# Schematics.net
KiCad netlist of a schematic drawn in EAGLE
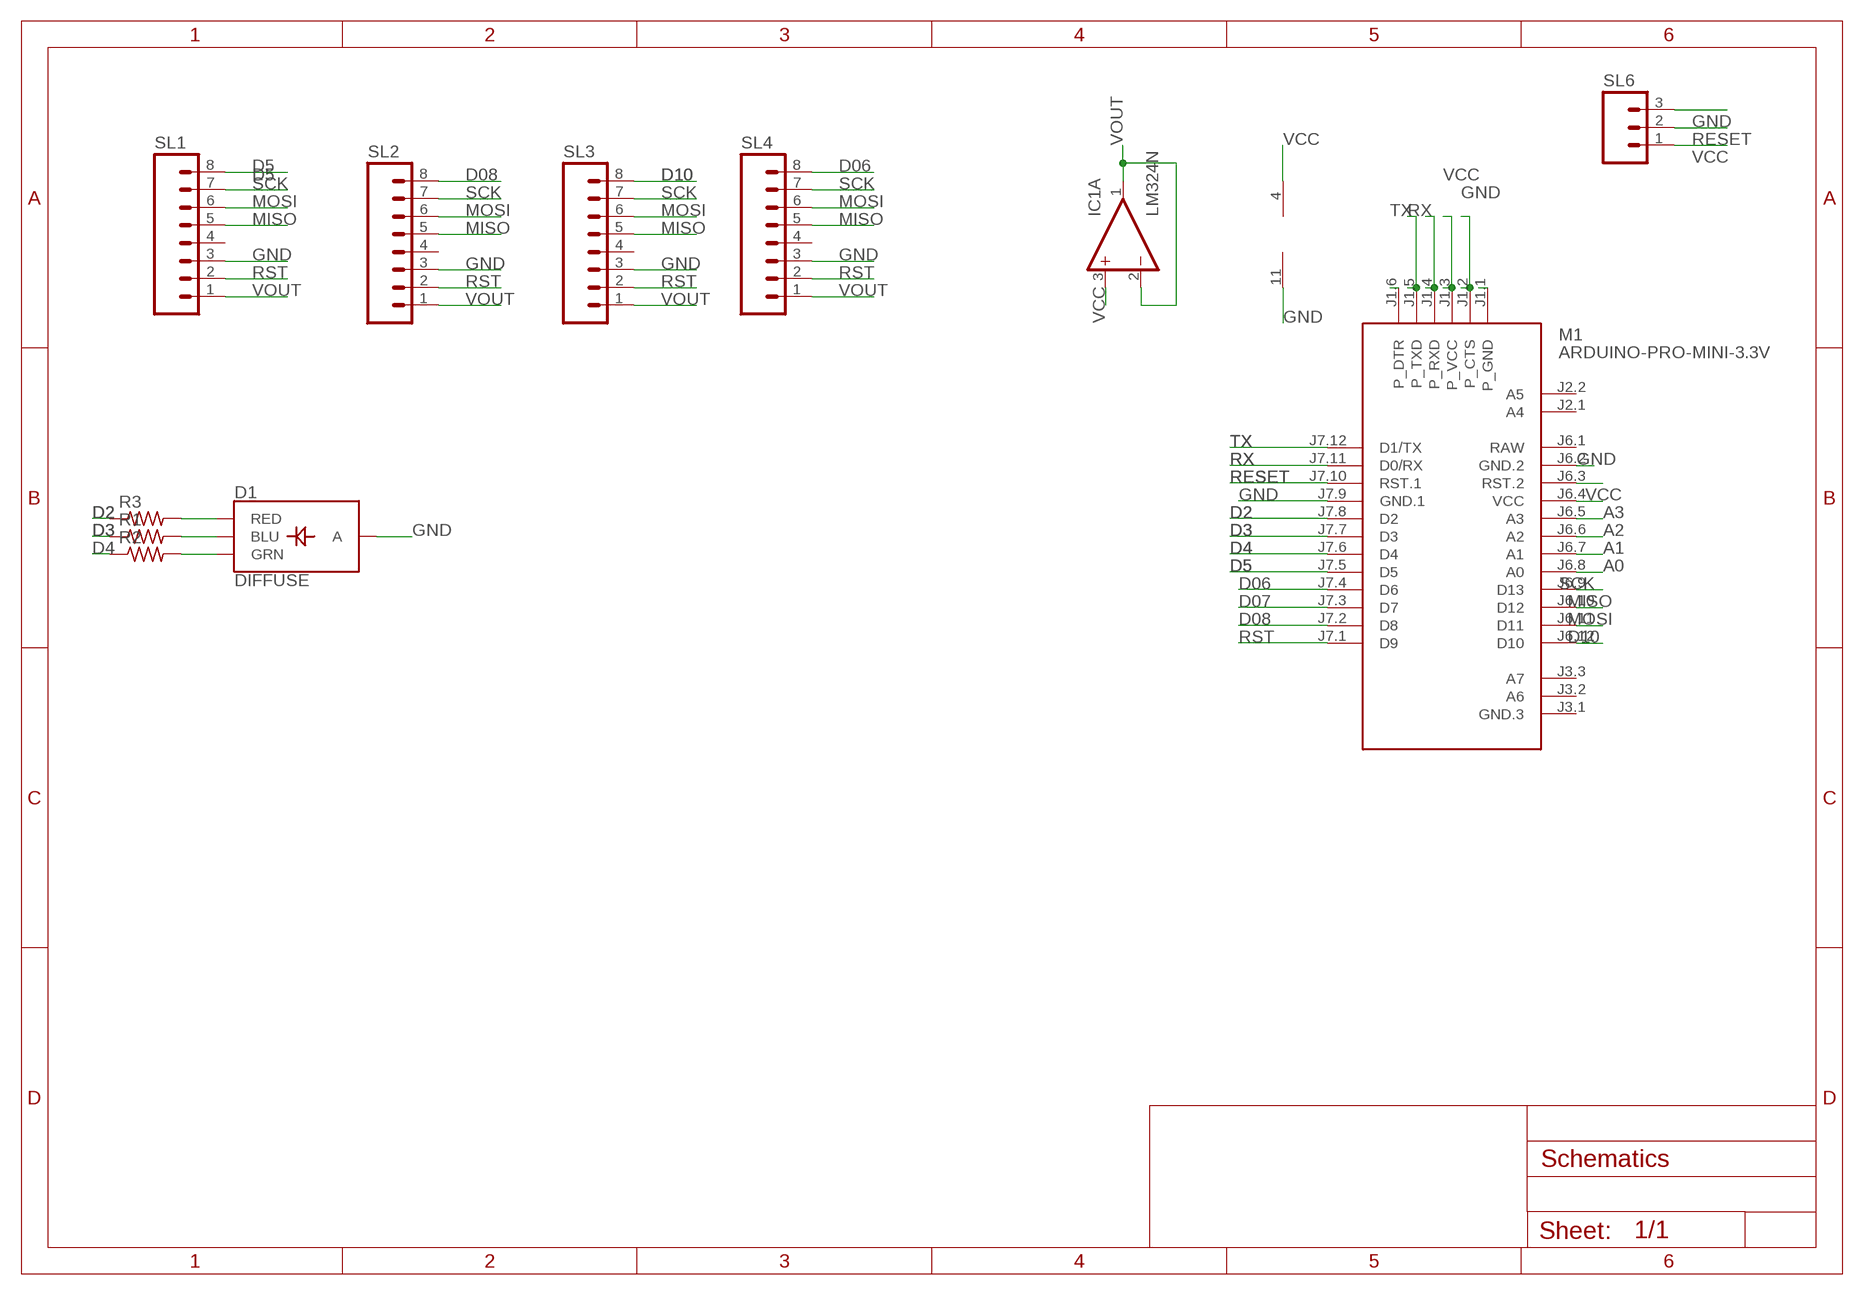
[diagram p0: schematic, sheet 1]

(export (version "E")
  (design (tool "Eeschema 10.0.6"))
  (components
    (comp (ref "D1")
      (value "DIFFUSE")
      (footprint "eagle-import:LED-RGB-THRU")
      (libsource (lib "eagle-import") (part "LED-RGB-CADIFFUSE"))
    )
    (comp (ref "IC1")
      (value "LM324N")
      (footprint "eagle-import:DIL14")
      (libsource (lib "eagle-import") (part "LM324N"))
    )
    (comp (ref "M1")
      (value "ARDUINO-PRO-MINI-3.3V")
      (footprint "eagle-import:ARDUINO-PRO-MINI")
      (libsource (lib "eagle-import") (part "ARDUINO-PRO-MINI-3.3V"))
    )
    (comp (ref "R1")
      (value "R-US_0204/7")
      (footprint "eagle-import:0204_7")
      (libsource (lib "eagle-import") (part "R-US_0204/7"))
    )
    (comp (ref "R2")
      (value "R-US_0204/7")
      (footprint "eagle-import:0204_7")
      (libsource (lib "eagle-import") (part "R-US_0204/7"))
    )
    (comp (ref "R3")
      (value "R-US_0204/7")
      (footprint "eagle-import:0204_7")
      (libsource (lib "eagle-import") (part "R-US_0204/7"))
    )
    (comp (ref "SL1")
      (value "M08")
      (footprint "eagle-import:08P")
      (libsource (lib "eagle-import") (part "M08"))
    )
    (comp (ref "SL2")
      (value "M08")
      (footprint "eagle-import:08P")
      (libsource (lib "eagle-import") (part "M08"))
    )
    (comp (ref "SL3")
      (value "M08")
      (footprint "eagle-import:08P")
      (libsource (lib "eagle-import") (part "M08"))
    )
    (comp (ref "SL4")
      (value "M08")
      (footprint "eagle-import:08P")
      (libsource (lib "eagle-import") (part "M08"))
    )
    (comp (ref "SL6")
      (value "M03")
      (footprint "eagle-import:03P")
      (libsource (lib "eagle-import") (part "M03"))
    )
  )
  (nets
    (net (code "1") (name "/A0") (class "Default")
      (node (ref "M1") (pin "J6.8") (pinfunction "A0_J6.8") (pintype "bidirectional"))
    )
    (net (code "2") (name "/A1") (class "Default")
      (node (ref "M1") (pin "J6.7") (pinfunction "A1_J6.7") (pintype "bidirectional"))
    )
    (net (code "3") (name "/A2") (class "Default")
      (node (ref "M1") (pin "J6.6") (pinfunction "A2_J6.6") (pintype "bidirectional"))
    )
    (net (code "4") (name "/A3") (class "Default")
      (node (ref "M1") (pin "J6.5") (pinfunction "A3_J6.5") (pintype "bidirectional"))
    )
    (net (code "5") (name "/D2") (class "Default")
      (node (ref "M1") (pin "J7.8") (pinfunction "D2_J7.8") (pintype "bidirectional"))
      (node (ref "R3") (pin "1") (pinfunction "1_1") (pintype "passive"))
    )
    (net (code "6") (name "/D3") (class "Default")
      (node (ref "M1") (pin "J7.7") (pinfunction "D3_J7.7") (pintype "bidirectional"))
      (node (ref "R1") (pin "1") (pinfunction "1_1") (pintype "passive"))
    )
    (net (code "7") (name "/D4") (class "Default")
      (node (ref "M1") (pin "J7.6") (pinfunction "D4_J7.6") (pintype "bidirectional"))
      (node (ref "R2") (pin "1") (pinfunction "1_1") (pintype "passive"))
    )
    (net (code "8") (name "/D5") (class "Default")
      (node (ref "M1") (pin "J7.5") (pinfunction "D5_J7.5") (pintype "bidirectional"))
      (node (ref "SL1") (pin "8") (pinfunction "8_8") (pintype "passive"))
    )
    (net (code "9") (name "/D06") (class "Default")
      (node (ref "M1") (pin "J7.4") (pinfunction "D6_J7.4") (pintype "bidirectional"))
      (node (ref "SL4") (pin "8") (pinfunction "8_8") (pintype "passive"))
    )
    (net (code "10") (name "/D07") (class "Default")
      (node (ref "M1") (pin "J7.3") (pinfunction "D7_J7.3") (pintype "bidirectional"))
    )
    (net (code "11") (name "/D08") (class "Default")
      (node (ref "M1") (pin "J7.2") (pinfunction "D8_J7.2") (pintype "bidirectional"))
      (node (ref "SL2") (pin "8") (pinfunction "8_8") (pintype "passive"))
    )
    (net (code "12") (name "/D10") (class "Default")
      (node (ref "M1") (pin "J6.12") (pinfunction "D10_J6.12") (pintype "bidirectional"))
      (node (ref "SL3") (pin "8") (pinfunction "8_8") (pintype "passive"))
    )
    (net (code "13") (name "/GND") (class "Default")
      (node (ref "D1") (pin "2") (pinfunction "A_2") (pintype "bidirectional"))
      (node (ref "IC1") (pin "11") (pinfunction "V-_11") (pintype "power_in"))
      (node (ref "M1") (pin "J1.2") (pinfunction "P_CTS_J1.2") (pintype "bidirectional"))
      (node (ref "M1") (pin "J6.2") (pinfunction "GND.2_J6.2") (pintype "power_in"))
      (node (ref "M1") (pin "J7.9") (pinfunction "GND.1_J7.9") (pintype "power_in"))
      (node (ref "SL1") (pin "3") (pinfunction "3_3") (pintype "passive"))
      (node (ref "SL2") (pin "3") (pinfunction "3_3") (pintype "passive"))
      (node (ref "SL3") (pin "3") (pinfunction "3_3") (pintype "passive"))
      (node (ref "SL4") (pin "3") (pinfunction "3_3") (pintype "passive"))
      (node (ref "SL6") (pin "3") (pinfunction "3_3") (pintype "passive"))
    )
    (net (code "14") (name "/MISO") (class "Default")
      (node (ref "M1") (pin "J6.10") (pinfunction "D12_J6.10") (pintype "bidirectional"))
      (node (ref "SL1") (pin "5") (pinfunction "5_5") (pintype "passive"))
      (node (ref "SL2") (pin "5") (pinfunction "5_5") (pintype "passive"))
      (node (ref "SL3") (pin "5") (pinfunction "5_5") (pintype "passive"))
      (node (ref "SL4") (pin "5") (pinfunction "5_5") (pintype "passive"))
    )
    (net (code "15") (name "/MOSI") (class "Default")
      (node (ref "M1") (pin "J6.11") (pinfunction "D11_J6.11") (pintype "bidirectional"))
      (node (ref "SL1") (pin "6") (pinfunction "6_6") (pintype "passive"))
      (node (ref "SL2") (pin "6") (pinfunction "6_6") (pintype "passive"))
      (node (ref "SL3") (pin "6") (pinfunction "6_6") (pintype "passive"))
      (node (ref "SL4") (pin "6") (pinfunction "6_6") (pintype "passive"))
    )
    (net (code "16") (name "/RAW") (class "Default")
      (node (ref "M1") (pin "J6.1") (pinfunction "RAW_J6.1") (pintype "power_in"))
    )
    (net (code "17") (name "/RESET") (class "Default")
      (node (ref "M1") (pin "J7.10") (pinfunction "RST.1_J7.10") (pintype "bidirectional"))
      (node (ref "SL6") (pin "2") (pinfunction "2_2") (pintype "passive"))
    )
    (net (code "18") (name "/RST") (class "Default")
      (node (ref "M1") (pin "J7.1") (pinfunction "D9_J7.1") (pintype "bidirectional"))
      (node (ref "SL1") (pin "2") (pinfunction "2_2") (pintype "passive"))
      (node (ref "SL2") (pin "2") (pinfunction "2_2") (pintype "passive"))
      (node (ref "SL3") (pin "2") (pinfunction "2_2") (pintype "passive"))
      (node (ref "SL4") (pin "2") (pinfunction "2_2") (pintype "passive"))
    )
    (net (code "19") (name "/RX") (class "Default")
      (node (ref "M1") (pin "J1.4") (pinfunction "P_RXD_J1.4") (pintype "bidirectional"))
      (node (ref "M1") (pin "J7.11") (pinfunction "D0/RX_J7.11") (pintype "bidirectional"))
    )
    (net (code "20") (name "/SCK") (class "Default")
      (node (ref "M1") (pin "J6.9") (pinfunction "D13_J6.9") (pintype "bidirectional"))
      (node (ref "SL1") (pin "7") (pinfunction "7_7") (pintype "passive"))
      (node (ref "SL2") (pin "7") (pinfunction "7_7") (pintype "passive"))
      (node (ref "SL3") (pin "7") (pinfunction "7_7") (pintype "passive"))
      (node (ref "SL4") (pin "7") (pinfunction "7_7") (pintype "passive"))
    )
    (net (code "21") (name "/TX") (class "Default")
      (node (ref "M1") (pin "J1.5") (pinfunction "P_TXD_J1.5") (pintype "bidirectional"))
      (node (ref "M1") (pin "J7.12") (pinfunction "D1/TX_J7.12") (pintype "bidirectional"))
    )
    (net (code "22") (name "/VCC") (class "Default")
      (node (ref "IC1") (pin "3") (pinfunction "+IN_3") (pintype "input"))
      (node (ref "IC1") (pin "4") (pinfunction "V+_4") (pintype "power_in"))
      (node (ref "M1") (pin "J1.3") (pinfunction "P_VCC_J1.3") (pintype "bidirectional"))
      (node (ref "M1") (pin "J6.4") (pinfunction "VCC_J6.4") (pintype "power_in"))
      (node (ref "SL6") (pin "1") (pinfunction "1_1") (pintype "passive"))
    )
    (net (code "23") (name "/VOUT") (class "Default")
      (node (ref "IC1") (pin "1") (pinfunction "OUT_1") (pintype "output"))
      (node (ref "IC1") (pin "2") (pinfunction "-IN_2") (pintype "input"))
      (node (ref "SL1") (pin "1") (pinfunction "1_1") (pintype "passive"))
      (node (ref "SL2") (pin "1") (pinfunction "1_1") (pintype "passive"))
      (node (ref "SL3") (pin "1") (pinfunction "1_1") (pintype "passive"))
      (node (ref "SL4") (pin "1") (pinfunction "1_1") (pintype "passive"))
    )
    (net (code "24") (name "Net-(D1-BLU)") (class "Default")
      (node (ref "D1") (pin "4") (pinfunction "BLU_4") (pintype "bidirectional"))
      (node (ref "R1") (pin "2") (pinfunction "2_2") (pintype "passive"))
    )
    (net (code "25") (name "Net-(D1-GRN)") (class "Default")
      (node (ref "D1") (pin "3") (pinfunction "GRN_3") (pintype "bidirectional"))
      (node (ref "R2") (pin "2") (pinfunction "2_2") (pintype "passive"))
    )
    (net (code "26") (name "Net-(D1-RED)") (class "Default")
      (node (ref "D1") (pin "1") (pinfunction "RED_1") (pintype "bidirectional"))
      (node (ref "R3") (pin "2") (pinfunction "2_2") (pintype "passive"))
    )
    (net (code "27") (name "unconnected-(M1-A4-PadJ2.1)") (class "Default")
      (node (ref "M1") (pin "J2.1") (pinfunction "A4_J2.1") (pintype "bidirectional"))
    )
    (net (code "28") (name "unconnected-(M1-A5-PadJ2.2)") (class "Default")
      (node (ref "M1") (pin "J2.2") (pinfunction "A5_J2.2") (pintype "bidirectional"))
    )
    (net (code "29") (name "unconnected-(M1-A6-PadJ3.2)") (class "Default")
      (node (ref "M1") (pin "J3.2") (pinfunction "A6_J3.2") (pintype "bidirectional"))
    )
    (net (code "30") (name "unconnected-(M1-A7-PadJ3.3)") (class "Default")
      (node (ref "M1") (pin "J3.3") (pinfunction "A7_J3.3") (pintype "bidirectional"))
    )
    (net (code "31") (name "unconnected-(M1-GND.3-PadJ3.1)") (class "Default")
      (node (ref "M1") (pin "J3.1") (pinfunction "GND.3_J3.1") (pintype "bidirectional"))
    )
    (net (code "32") (name "unconnected-(M1-P_DTR-PadJ1.6)") (class "Default")
      (node (ref "M1") (pin "J1.6") (pinfunction "P_DTR_J1.6") (pintype "bidirectional"))
    )
    (net (code "33") (name "unconnected-(M1-P_GND-PadJ1.1)") (class "Default")
      (node (ref "M1") (pin "J1.1") (pinfunction "P_GND_J1.1") (pintype "bidirectional"))
    )
    (net (code "34") (name "unconnected-(M1-RST.2-PadJ6.3)") (class "Default")
      (node (ref "M1") (pin "J6.3") (pinfunction "RST.2_J6.3") (pintype "bidirectional"))
    )
    (net (code "35") (name "unconnected-(SL1-Pad4)") (class "Default")
      (node (ref "SL1") (pin "4") (pinfunction "4_4") (pintype "passive"))
    )
    (net (code "36") (name "unconnected-(SL2-Pad4)") (class "Default")
      (node (ref "SL2") (pin "4") (pinfunction "4_4") (pintype "passive"))
    )
    (net (code "37") (name "unconnected-(SL3-Pad4)") (class "Default")
      (node (ref "SL3") (pin "4") (pinfunction "4_4") (pintype "passive"))
    )
    (net (code "38") (name "unconnected-(SL4-Pad4)") (class "Default")
      (node (ref "SL4") (pin "4") (pinfunction "4_4") (pintype "passive"))
    )
  )
)
